# 0-10V_Converter.net
KiCad netlist of a schematic drawn in Altium Designer
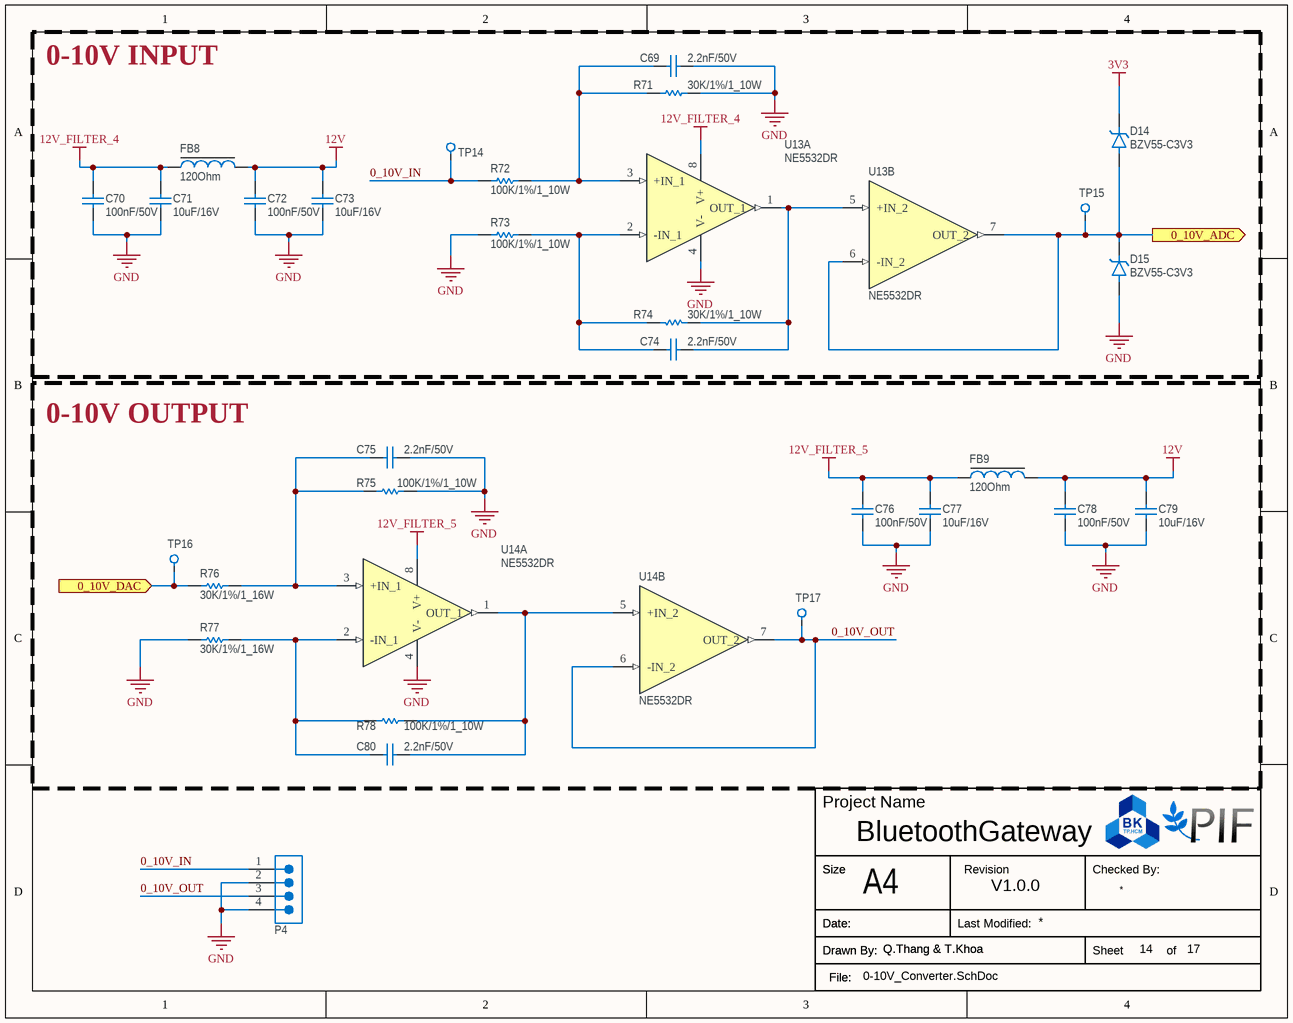
[diagram p0: 0-10V_Converter.SchDoc]

(export (version "E")
  (design (tool "Eeschema 10.0.6"))
  (components
    (comp (ref "C69")
      (value "2.2nF/50V")
      (footprint "CAP_0603")
      (description "CAP, size 0603, 2.2nF, 50V")
      (fields (field (name "SUPPLY PART NUMBER") "CC0603KRX7R9BB222"))
      (libsource (lib "BluetoothTracking") (part "Ceramic_Cap_2.2nF_50V_0603"))
    )
    (comp (ref "C70")
      (value "100nF/50V")
      (footprint "CAP_0603")
      (description "CAP, size 0603, 100nF, 50V")
      (fields (field (name "SUPPLY PART NUMBER") "Tụ Gốm 0603 100nF (0.1uF) 50V"))
      (libsource (lib "BluetoothTracking") (part "Ceramic_Cap_100nF_50V_0603"))
    )
    (comp (ref "C71")
      (value "10uF/16V")
      (footprint "CAP_0603")
      (description "CAP, size 0603, 10uF, 16V")
      (fields (field (name "SUPPLY PART NUMBER") "Tụ Gốm 0603 10uF 16V"))
      (libsource (lib "BluetoothTracking") (part "Ceramic_Cap_10uF_16V_0603"))
    )
    (comp (ref "C72")
      (value "100nF/50V")
      (footprint "CAP_0603")
      (description "CAP, size 0603, 100nF, 50V")
      (fields (field (name "SUPPLY PART NUMBER") "Tụ Gốm 0603 100nF (0.1uF) 50V"))
      (libsource (lib "BluetoothTracking") (part "Ceramic_Cap_100nF_50V_0603"))
    )
    (comp (ref "C73")
      (value "10uF/16V")
      (footprint "CAP_0603")
      (description "CAP, size 0603, 10uF, 16V")
      (fields (field (name "SUPPLY PART NUMBER") "Tụ Gốm 0603 10uF 16V"))
      (libsource (lib "BluetoothTracking") (part "Ceramic_Cap_10uF_16V_0603"))
    )
    (comp (ref "C74")
      (value "2.2nF/50V")
      (footprint "CAP_0603")
      (description "CAP, size 0603, 2.2nF, 50V")
      (fields (field (name "SUPPLY PART NUMBER") "CC0603KRX7R9BB222"))
      (libsource (lib "BluetoothTracking") (part "Ceramic_Cap_2.2nF_50V_0603"))
    )
    (comp (ref "C75")
      (value "2.2nF/50V")
      (footprint "CAP_0603")
      (description "CAP, size 0603, 2.2nF, 50V")
      (fields (field (name "SUPPLY PART NUMBER") "CC0603KRX7R9BB222"))
      (libsource (lib "BluetoothTracking") (part "Ceramic_Cap_2.2nF_50V_0603"))
    )
    (comp (ref "C76")
      (value "100nF/50V")
      (footprint "CAP_0603")
      (description "CAP, size 0603, 100nF, 50V")
      (fields (field (name "SUPPLY PART NUMBER") "Tụ Gốm 0603 100nF (0.1uF) 50V"))
      (libsource (lib "BluetoothTracking") (part "Ceramic_Cap_100nF_50V_0603"))
    )
    (comp (ref "C77")
      (value "10uF/16V")
      (footprint "CAP_0603")
      (description "CAP, size 0603, 10uF, 16V")
      (fields (field (name "SUPPLY PART NUMBER") "Tụ Gốm 0603 10uF 16V"))
      (libsource (lib "BluetoothTracking") (part "Ceramic_Cap_10uF_16V_0603"))
    )
    (comp (ref "C78")
      (value "100nF/50V")
      (footprint "CAP_0603")
      (description "CAP, size 0603, 100nF, 50V")
      (fields (field (name "SUPPLY PART NUMBER") "Tụ Gốm 0603 100nF (0.1uF) 50V"))
      (libsource (lib "BluetoothTracking") (part "Ceramic_Cap_100nF_50V_0603"))
    )
    (comp (ref "C79")
      (value "10uF/16V")
      (footprint "CAP_0603")
      (description "CAP, size 0603, 10uF, 16V")
      (fields (field (name "SUPPLY PART NUMBER") "Tụ Gốm 0603 10uF 16V"))
      (libsource (lib "BluetoothTracking") (part "Ceramic_Cap_10uF_16V_0603"))
    )
    (comp (ref "C80")
      (value "2.2nF/50V")
      (footprint "CAP_0603")
      (description "CAP, size 0603, 2.2nF, 50V")
      (fields (field (name "SUPPLY PART NUMBER") "CC0603KRX7R9BB222"))
      (libsource (lib "BluetoothTracking") (part "Ceramic_Cap_2.2nF_50V_0603"))
    )
    (comp (ref "D14")
      (value "BZV55-C3V3")
      (footprint "SOD-80")
      (description "DIODE ZENER 3.3V 500 mW")
      (libsource (lib "BluetoothTracking") (part "Diode_BZV55C3V3"))
    )
    (comp (ref "D15")
      (value "BZV55-C3V3")
      (footprint "SOD-80")
      (description "DIODE ZENER 3.3V 500 mW")
      (libsource (lib "BluetoothTracking") (part "Diode_BZV55C3V3"))
    )
    (comp (ref "FB8")
      (value "120Ohm")
      (footprint "Ferrite_Bead_0805")
      (description "Ferrite Bead, size 0805, 120Ohm, 2A")
      (fields (field (name "SUPPLY PART NUMBER") "CBW201209U121T Ferrite Beads 2A 120 Ohm 0805"))
      (libsource (lib "BluetoothTracking") (part "Ferrite_Bead_120Ohm_2A_0805"))
    )
    (comp (ref "FB9")
      (value "120Ohm")
      (footprint "Ferrite_Bead_0805")
      (description "Ferrite Bead, size 0805, 120Ohm, 2A")
      (fields (field (name "SUPPLY PART NUMBER") "CBW201209U121T Ferrite Beads 2A 120 Ohm 0805"))
      (libsource (lib "BluetoothTracking") (part "Ferrite_Bead_120Ohm_2A_0805"))
    )
    (comp (ref "P4")
      (value "3.81mm_4P")
      (footprint "Terminal_Block_3.81mm_4P")
      (description "Terminal Block THT, pitch 3.81mm, 4p, 300V 10A")
      (fields
        (field (name "SUPPLY PART NUMBER") "UL-3.81-4-R Terminal Block Plug-in Hàn PCB 4 Chân Cong 3.81mm 300V 10A ULO")
      )
      (libsource (lib "BluetoothTracking") (part "Terminal_Block_3.81mm_4P"))
    )
    (comp (ref "R71")
      (value "30K/1%/1_10W")
      (footprint "Resistor_0603")
      (description "Resistor 0603 30KOhm 1% 1_10W")
      (fields (field (name "SUPPLY PART NUMBER") "Điện Trở 30 KOhm 0603 1%"))
      (libsource (lib "BluetoothTracking") (part "Res_30K_0603_1%"))
    )
    (comp (ref "R72")
      (value "100K/1%/1_10W")
      (footprint "Resistor_0603")
      (description "Resistor 0603 100KOhm 1% 1_10W")
      (fields (field (name "SUPPLY PART NUMBER") "Điện Trở 100 KOhm 0603 1%"))
      (libsource (lib "BluetoothTracking") (part "Res_100K_0603_1%"))
    )
    (comp (ref "R73")
      (value "100K/1%/1_10W")
      (footprint "Resistor_0603")
      (description "Resistor 0603 100KOhm 1% 1_10W")
      (fields (field (name "SUPPLY PART NUMBER") "Điện Trở 100 KOhm 0603 1%"))
      (libsource (lib "BluetoothTracking") (part "Res_100K_0603_1%"))
    )
    (comp (ref "R74")
      (value "30K/1%/1_10W")
      (footprint "Resistor_0603")
      (description "Resistor 0603 30KOhm 1% 1_10W")
      (fields (field (name "SUPPLY PART NUMBER") "Điện Trở 30 KOhm 0603 1%"))
      (libsource (lib "BluetoothTracking") (part "Res_30K_0603_1%"))
    )
    (comp (ref "R75")
      (value "100K/1%/1_10W")
      (footprint "Resistor_0603")
      (description "Resistor 0603 100KOhm 1% 1_10W")
      (fields (field (name "SUPPLY PART NUMBER") "Điện Trở 100 KOhm 0603 1%"))
      (libsource (lib "BluetoothTracking") (part "Res_100K_0603_1%"))
    )
    (comp (ref "R76")
      (value "30K/1%/1_16W")
      (footprint "RESISTOR_0402")
      (description "Resistor 0402 30KOhm 1% 1_16W")
      (fields (field (name "SUPPLY PART NUMBER") "Điện Trở 30 KOhm 0402 1%"))
      (libsource (lib "BluetoothTracking") (part "Res_30K_0402_1%"))
    )
    (comp (ref "R77")
      (value "30K/1%/1_16W")
      (footprint "RESISTOR_0402")
      (description "Resistor 0402 30KOhm 1% 1_16W")
      (fields (field (name "SUPPLY PART NUMBER") "Điện Trở 30 KOhm 0402 1%"))
      (libsource (lib "BluetoothTracking") (part "Res_30K_0402_1%"))
    )
    (comp (ref "R78")
      (value "100K/1%/1_10W")
      (footprint "Resistor_0603")
      (description "Resistor 0603 100KOhm 1% 1_10W")
      (fields (field (name "SUPPLY PART NUMBER") "Điện Trở 100 KOhm 0603 1%"))
      (libsource (lib "BluetoothTracking") (part "Res_100K_0603_1%"))
    )
    (comp (ref "TP14")
      (value "0-10V_IN")
      (footprint "TestPoint_THTPad_D1.5mm_Drill0.7mm")
      (description "Test Point TEST-1BK")
      (libsource (lib "BluetoothTracking") (part "Testpoint_TH"))
    )
    (comp (ref "TP15")
      (value "0-10V_ADC")
      (footprint "TestPoint_THTPad_D1.5mm_Drill0.7mm")
      (description "Test Point TEST-1BK")
      (libsource (lib "BluetoothTracking") (part "Testpoint_TH"))
    )
    (comp (ref "TP16")
      (value "0-10V_DAC")
      (footprint "TestPoint_THTPad_D1.5mm_Drill0.7mm")
      (description "Test Point TEST-1BK")
      (libsource (lib "BluetoothTracking") (part "Testpoint_TH"))
    )
    (comp (ref "TP17")
      (value "0-10V_Output")
      (footprint "TestPoint_THTPad_D1.5mm_Drill0.7mm")
      (description "Test Point TEST-1BK")
      (libsource (lib "BluetoothTracking") (part "Testpoint_TH"))
    )
    (comp (ref "U13")
      (value "NE5532DR")
      (footprint "SOIC-8")
      (description "Low Noise Single/Dual Operational Amplifier - SOIC-8")
      (libsource (lib "BluetoothTracking") (part "NE5532DR"))
    )
    (comp (ref "U14")
      (value "NE5532DR")
      (footprint "SOIC-8")
      (description "Low Noise Single/Dual Operational Amplifier - SOIC-8")
      (libsource (lib "BluetoothTracking") (part "NE5532DR"))
    )
  )
  (nets
    (net (code "1") (name "/0_10V_ADC") (class "Default")
      (node (ref "D14") (pin "A") (pinfunction "A_A") (pintype "passive"))
      (node (ref "D15") (pin "C") (pinfunction "C_C") (pintype "passive"))
      (node (ref "TP15") (pin "1") (pinfunction "1_1") (pintype "passive"))
      (node (ref "U13") (pin "6") (pinfunction "-IN_2_6") (pintype "input"))
      (node (ref "U13") (pin "7") (pinfunction "OUT_2_7") (pintype "output"))
    )
    (net (code "2") (name "/0_10V_DAC") (class "Default")
      (node (ref "R76") (pin "1") (pinfunction "1_1") (pintype "passive"))
      (node (ref "TP16") (pin "1") (pinfunction "1_1") (pintype "passive"))
    )
    (net (code "3") (name "/0_10V_IN") (class "Default")
      (node (ref "P4") (pin "1") (pinfunction "1_1") (pintype "passive"))
      (node (ref "R72") (pin "1") (pinfunction "1_1") (pintype "passive"))
      (node (ref "TP14") (pin "1") (pinfunction "1_1") (pintype "passive"))
    )
    (net (code "4") (name "/0_10V_OUT") (class "Default")
      (node (ref "P4") (pin "3") (pinfunction "3_3") (pintype "passive"))
      (node (ref "TP17") (pin "1") (pinfunction "1_1") (pintype "passive"))
      (node (ref "U14") (pin "6") (pinfunction "-IN_2_6") (pintype "input"))
      (node (ref "U14") (pin "7") (pinfunction "OUT_2_7") (pintype "output"))
    )
    (net (code "5") (name "3V3") (class "Default")
      (node (ref "D14") (pin "C") (pinfunction "C_C") (pintype "passive"))
    )
    (net (code "6") (name "12V") (class "Default")
      (node (ref "C72") (pin "2") (pinfunction "2_2") (pintype "passive"))
      (node (ref "C73") (pin "2") (pinfunction "2_2") (pintype "passive"))
      (node (ref "C78") (pin "2") (pinfunction "2_2") (pintype "passive"))
      (node (ref "C79") (pin "2") (pinfunction "2_2") (pintype "passive"))
      (node (ref "FB8") (pin "2") (pinfunction "2_2") (pintype "passive"))
      (node (ref "FB9") (pin "2") (pinfunction "2_2") (pintype "passive"))
    )
    (net (code "7") (name "12V_FILTER_4") (class "Default")
      (node (ref "C70") (pin "2") (pinfunction "2_2") (pintype "passive"))
      (node (ref "C71") (pin "2") (pinfunction "2_2") (pintype "passive"))
      (node (ref "FB8") (pin "1") (pinfunction "1_1") (pintype "passive"))
      (node (ref "U13") (pin "8") (pinfunction "V+_8") (pintype "power_in"))
    )
    (net (code "8") (name "12V_FILTER_5") (class "Default")
      (node (ref "C76") (pin "2") (pinfunction "2_2") (pintype "passive"))
      (node (ref "C77") (pin "2") (pinfunction "2_2") (pintype "passive"))
      (node (ref "FB9") (pin "1") (pinfunction "1_1") (pintype "passive"))
      (node (ref "U14") (pin "8") (pinfunction "V+_8") (pintype "power_in"))
    )
    (net (code "9") (name "GND") (class "Default")
      (node (ref "C69") (pin "2") (pinfunction "2_2") (pintype "passive"))
      (node (ref "C70") (pin "1") (pinfunction "1_1") (pintype "passive"))
      (node (ref "C71") (pin "1") (pinfunction "1_1") (pintype "passive"))
      (node (ref "C72") (pin "1") (pinfunction "1_1") (pintype "passive"))
      (node (ref "C73") (pin "1") (pinfunction "1_1") (pintype "passive"))
      (node (ref "C75") (pin "2") (pinfunction "2_2") (pintype "passive"))
      (node (ref "C76") (pin "1") (pinfunction "1_1") (pintype "passive"))
      (node (ref "C77") (pin "1") (pinfunction "1_1") (pintype "passive"))
      (node (ref "C78") (pin "1") (pinfunction "1_1") (pintype "passive"))
      (node (ref "C79") (pin "1") (pinfunction "1_1") (pintype "passive"))
      (node (ref "D15") (pin "A") (pinfunction "A_A") (pintype "passive"))
      (node (ref "P4") (pin "2") (pinfunction "2_2") (pintype "passive"))
      (node (ref "P4") (pin "4") (pinfunction "4_4") (pintype "passive"))
      (node (ref "R71") (pin "2") (pinfunction "2_2") (pintype "passive"))
      (node (ref "R73") (pin "1") (pinfunction "1_1") (pintype "passive"))
      (node (ref "R75") (pin "2") (pinfunction "2_2") (pintype "passive"))
      (node (ref "R77") (pin "1") (pinfunction "1_1") (pintype "passive"))
      (node (ref "U13") (pin "4") (pinfunction "V-_4") (pintype "power_in"))
      (node (ref "U14") (pin "4") (pinfunction "V-_4") (pintype "power_in"))
    )
    (net (code "10") (name "Net-(U13A-+IN_1)") (class "Default")
      (node (ref "C69") (pin "1") (pinfunction "1_1") (pintype "passive"))
      (node (ref "R71") (pin "1") (pinfunction "1_1") (pintype "passive"))
      (node (ref "R72") (pin "2") (pinfunction "2_2") (pintype "passive"))
      (node (ref "U13") (pin "3") (pinfunction "+IN_1_3") (pintype "input"))
    )
    (net (code "11") (name "Net-(U13A--IN_1)") (class "Default")
      (node (ref "C74") (pin "1") (pinfunction "1_1") (pintype "passive"))
      (node (ref "R73") (pin "2") (pinfunction "2_2") (pintype "passive"))
      (node (ref "R74") (pin "1") (pinfunction "1_1") (pintype "passive"))
      (node (ref "U13") (pin "2") (pinfunction "-IN_1_2") (pintype "input"))
    )
    (net (code "12") (name "Net-(U13A-OUT_1)") (class "Default")
      (node (ref "C74") (pin "2") (pinfunction "2_2") (pintype "passive"))
      (node (ref "R74") (pin "2") (pinfunction "2_2") (pintype "passive"))
      (node (ref "U13") (pin "1") (pinfunction "OUT_1_1") (pintype "output"))
      (node (ref "U13") (pin "5") (pinfunction "+IN_2_5") (pintype "input"))
    )
    (net (code "13") (name "Net-(U14A-+IN_1)") (class "Default")
      (node (ref "C75") (pin "1") (pinfunction "1_1") (pintype "passive"))
      (node (ref "R75") (pin "1") (pinfunction "1_1") (pintype "passive"))
      (node (ref "R76") (pin "2") (pinfunction "2_2") (pintype "passive"))
      (node (ref "U14") (pin "3") (pinfunction "+IN_1_3") (pintype "input"))
    )
    (net (code "14") (name "Net-(U14A--IN_1)") (class "Default")
      (node (ref "C80") (pin "1") (pinfunction "1_1") (pintype "passive"))
      (node (ref "R77") (pin "2") (pinfunction "2_2") (pintype "passive"))
      (node (ref "R78") (pin "1") (pinfunction "1_1") (pintype "passive"))
      (node (ref "U14") (pin "2") (pinfunction "-IN_1_2") (pintype "input"))
    )
    (net (code "15") (name "Net-(U14A-OUT_1)") (class "Default")
      (node (ref "C80") (pin "2") (pinfunction "2_2") (pintype "passive"))
      (node (ref "R78") (pin "2") (pinfunction "2_2") (pintype "passive"))
      (node (ref "U14") (pin "1") (pinfunction "OUT_1_1") (pintype "output"))
      (node (ref "U14") (pin "5") (pinfunction "+IN_2_5") (pintype "input"))
    )
  )
)
